# outdoor-sensor.net
KiCad netlist of a schematic drawn in EAGLE
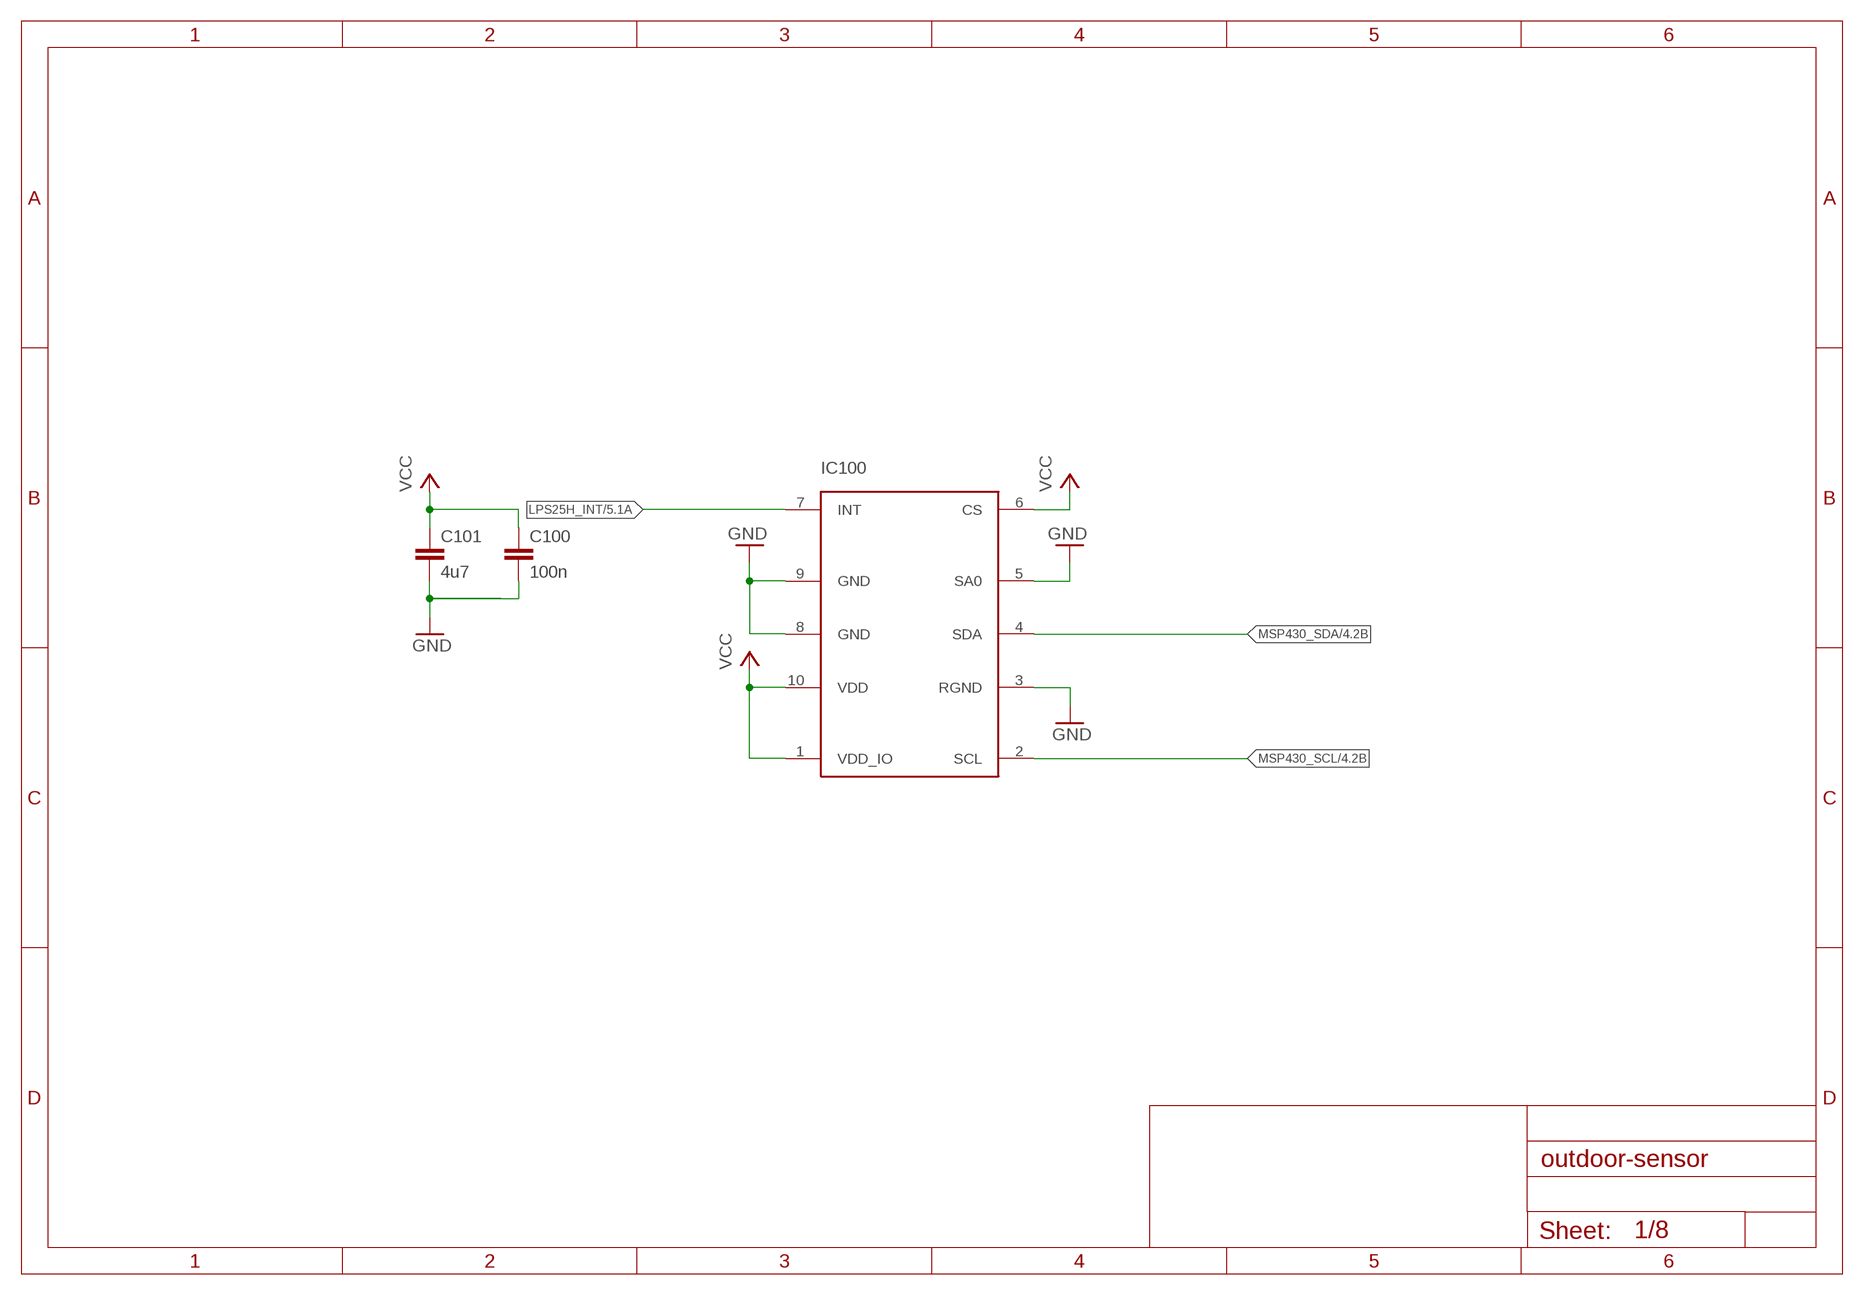
[diagram p0: schematic, sheet 1]
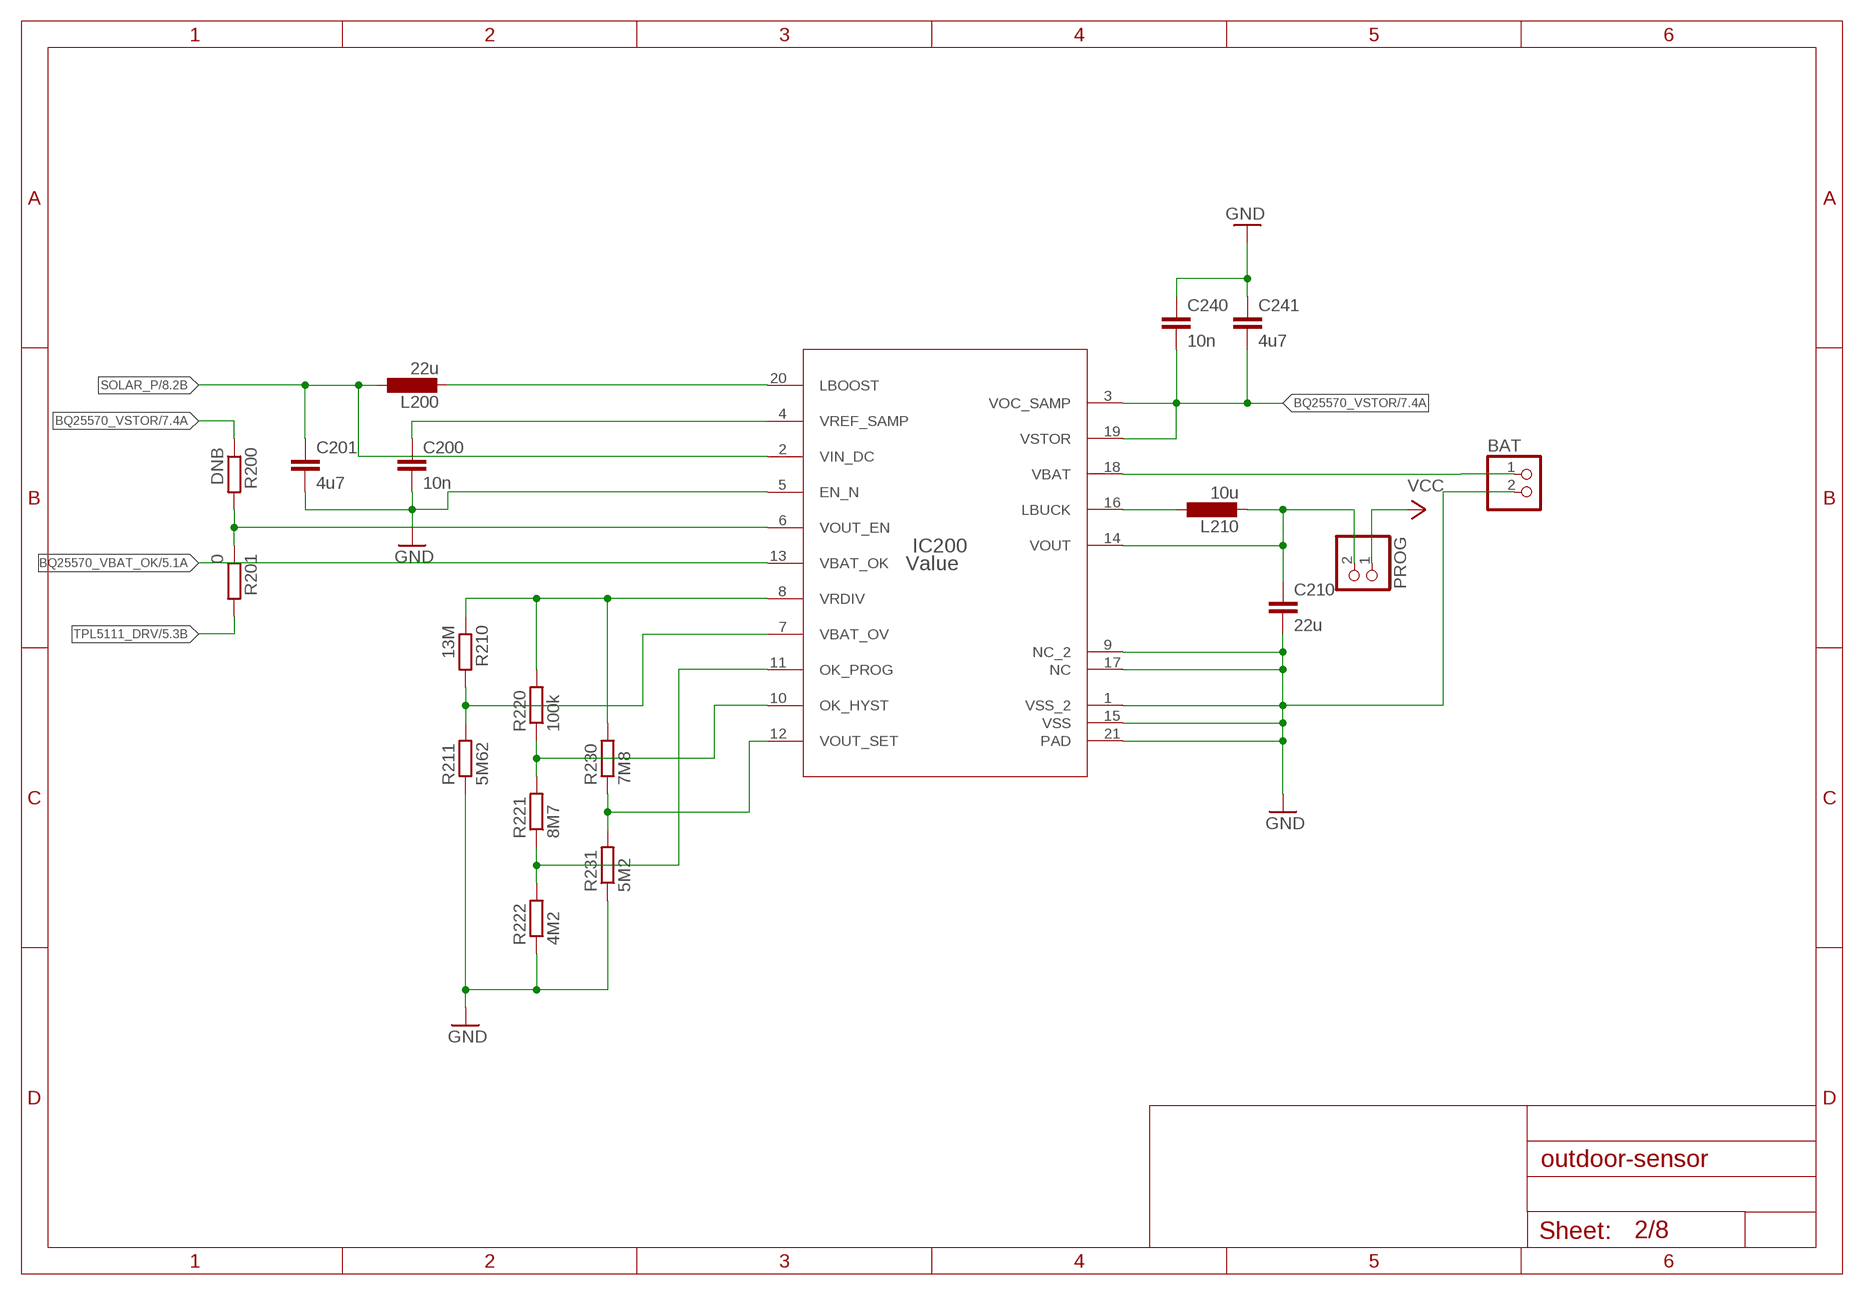
[diagram p1: schematic, sheet 2]
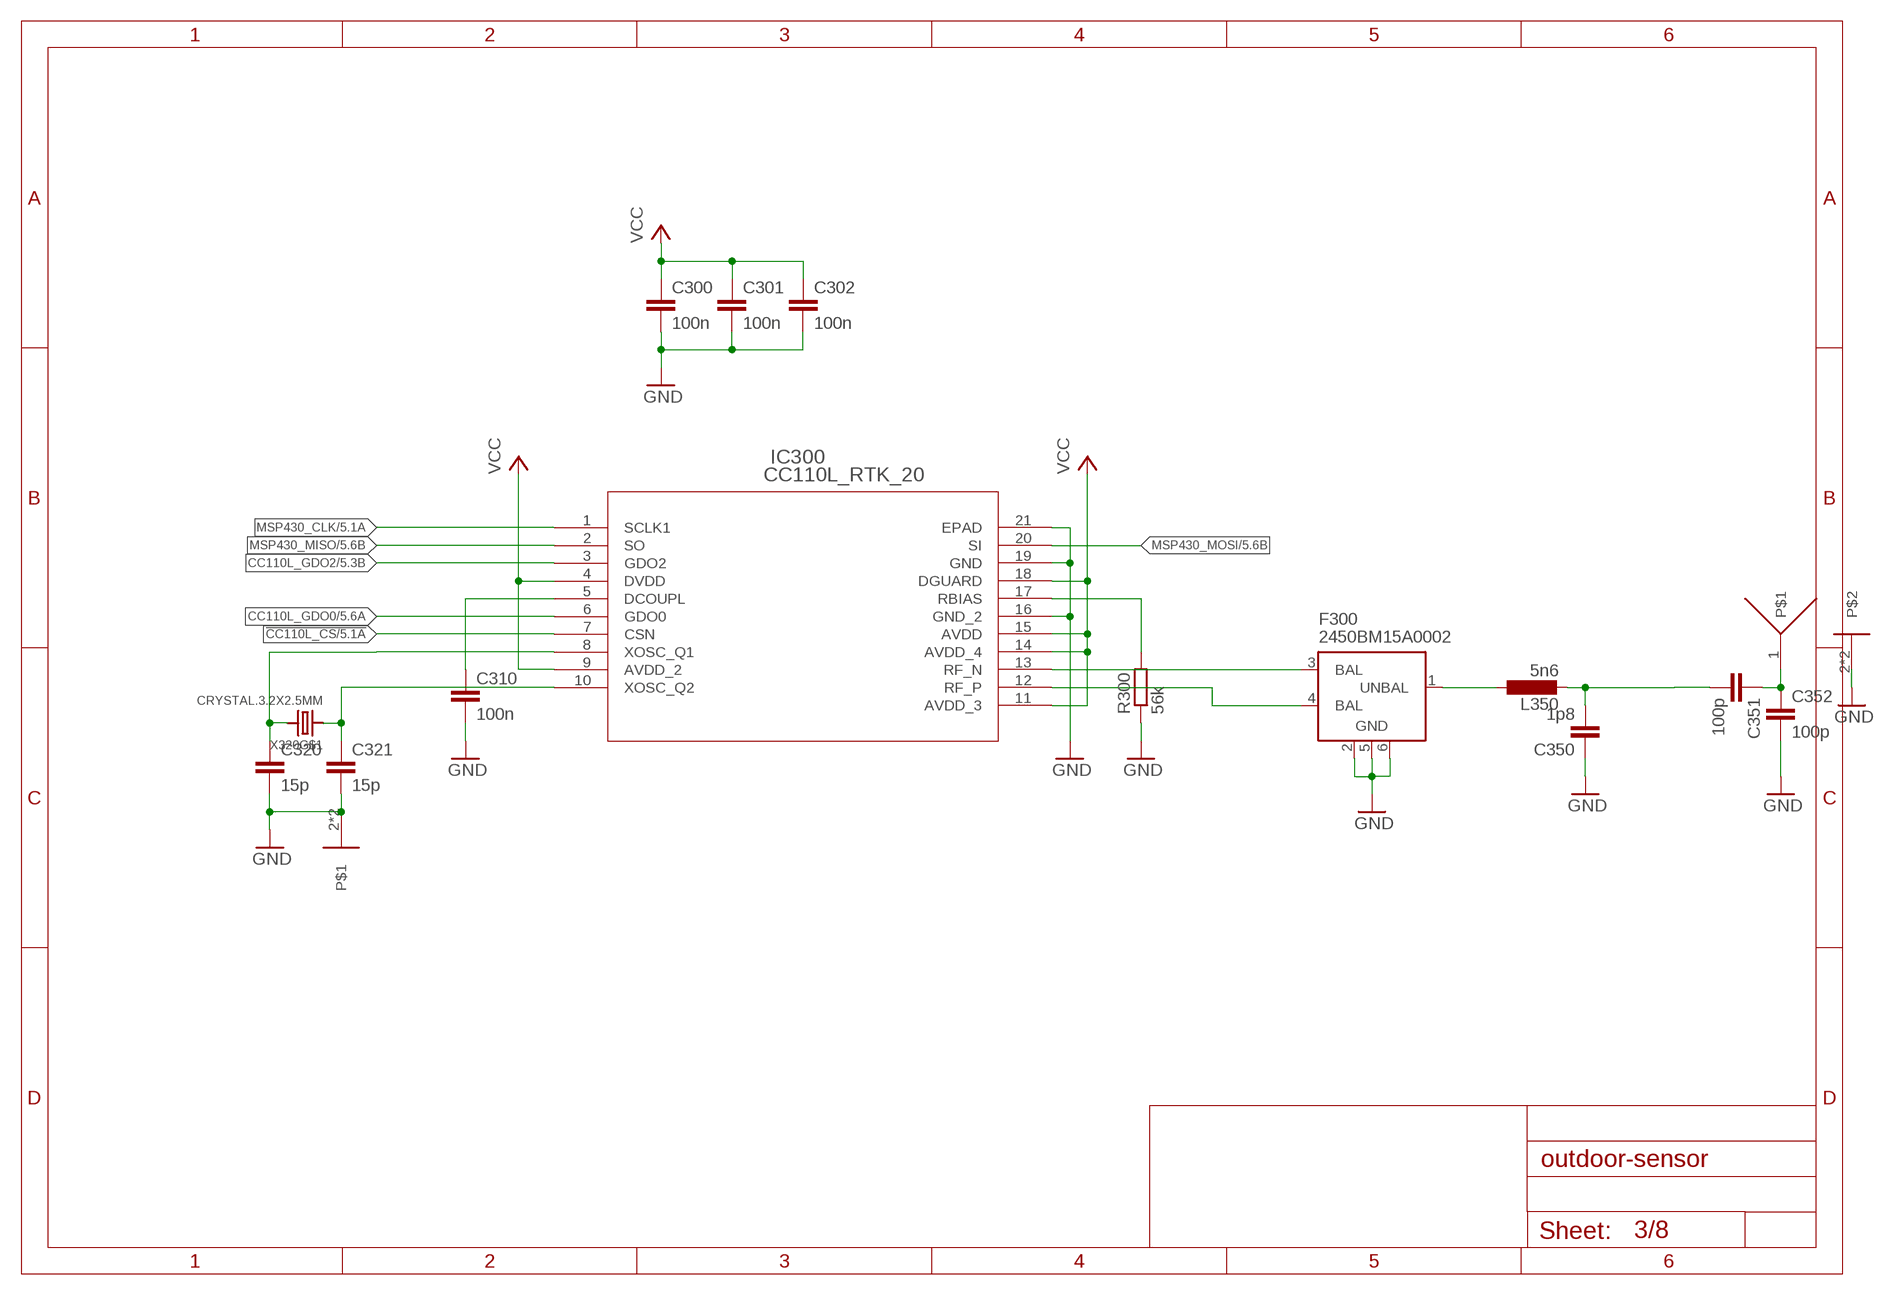
[diagram p2: schematic, sheet 3]
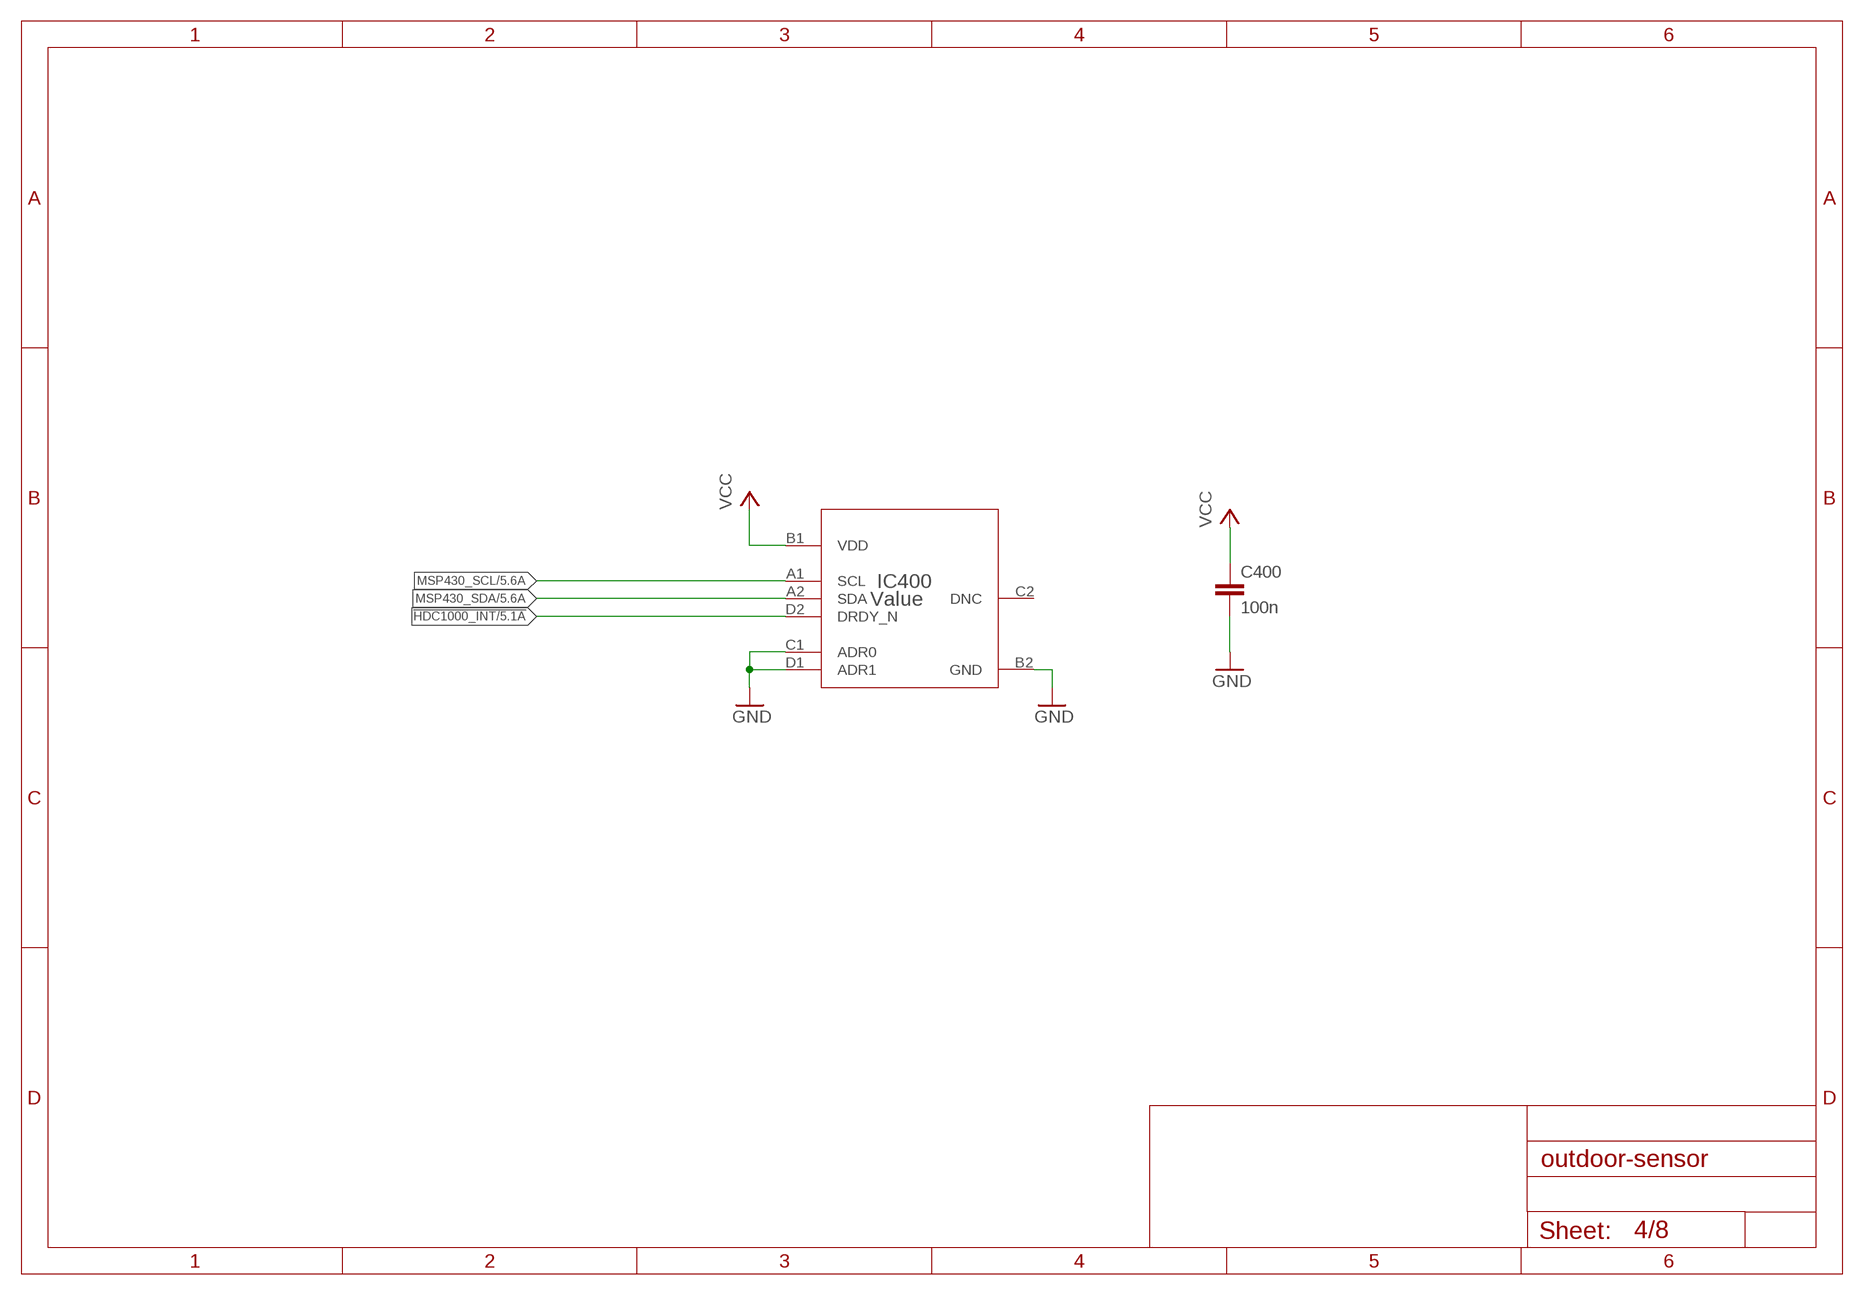
[diagram p3: schematic, sheet 4]
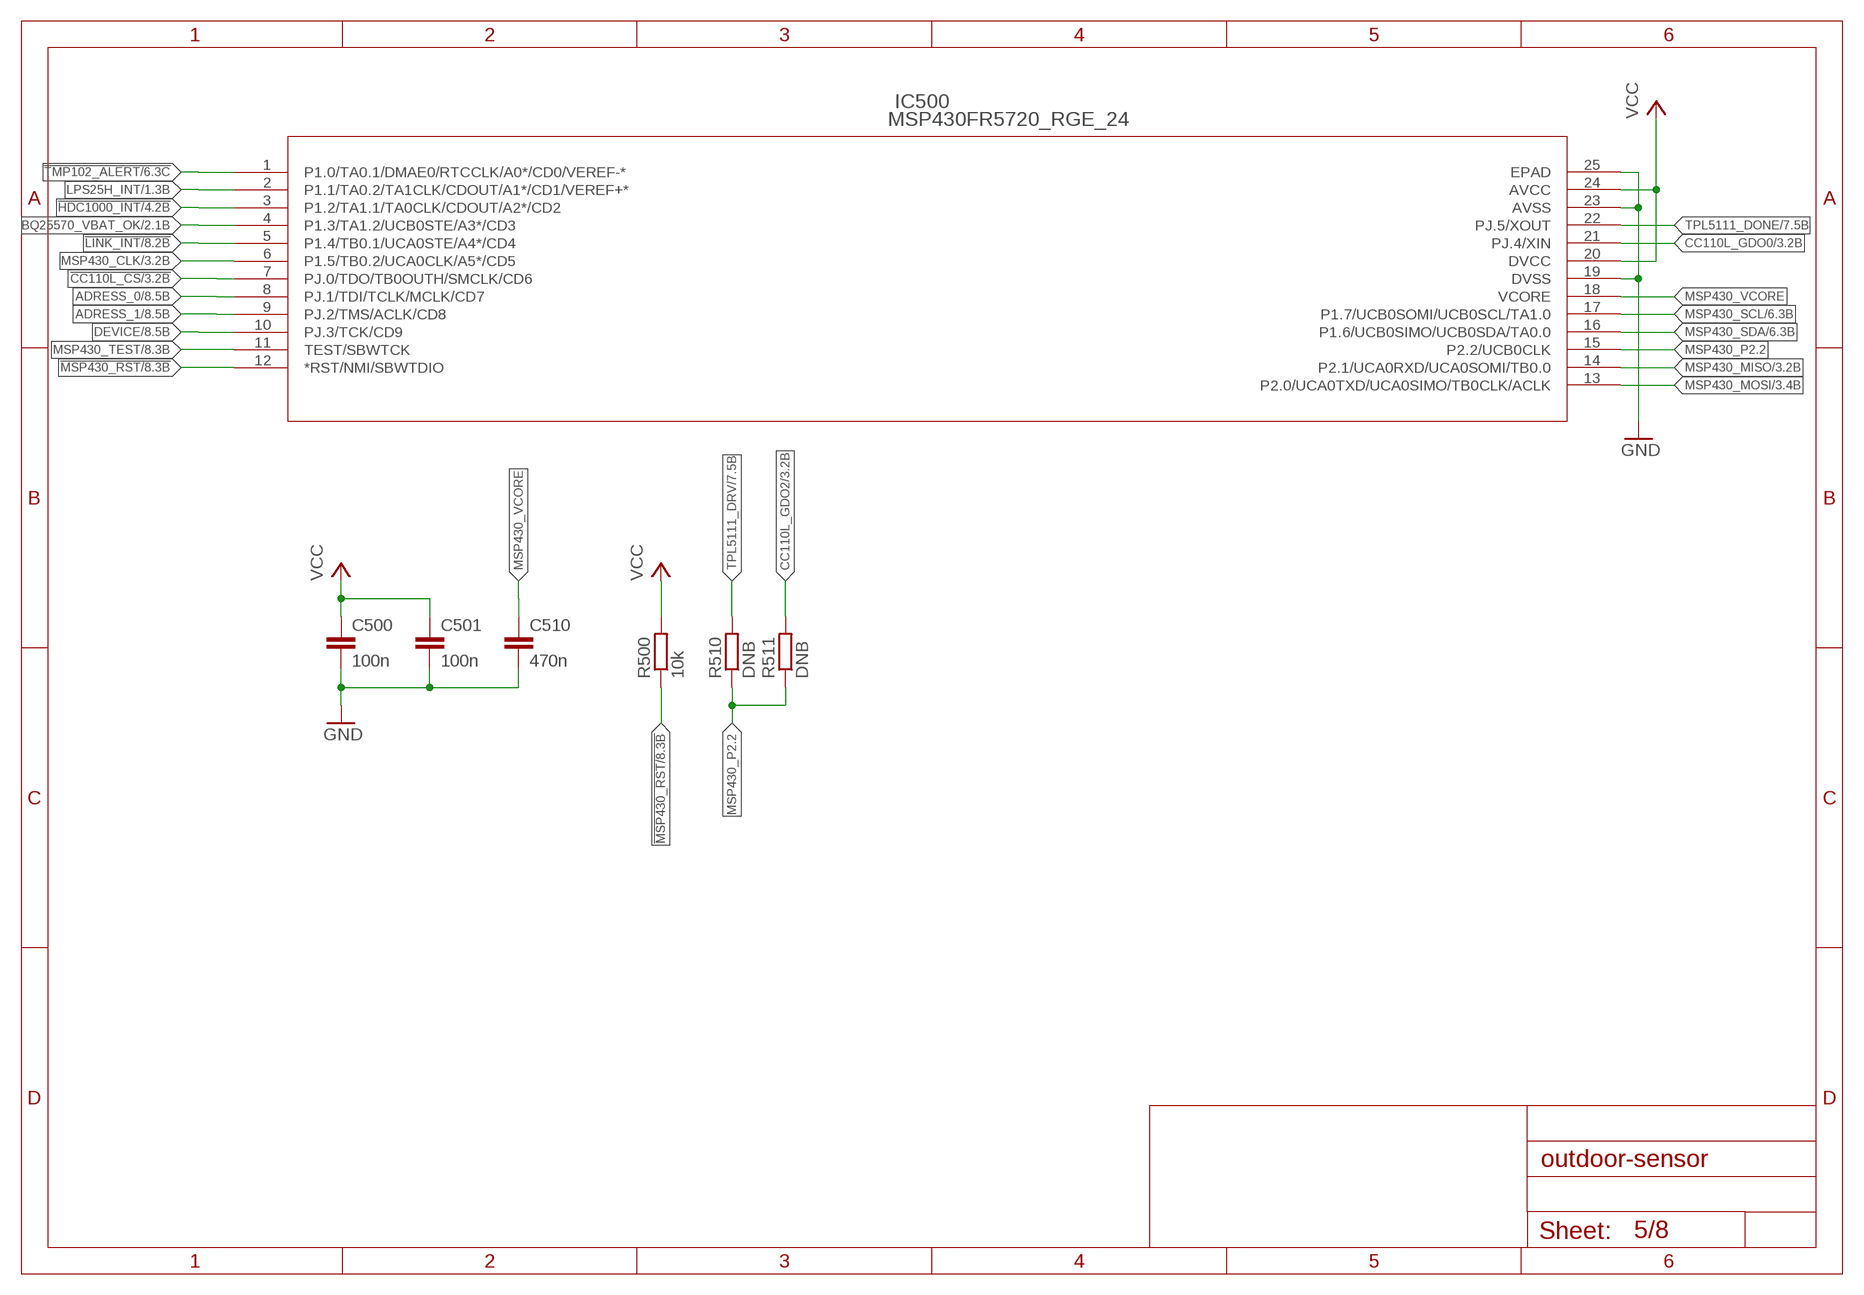
[diagram p4: schematic, sheet 5]
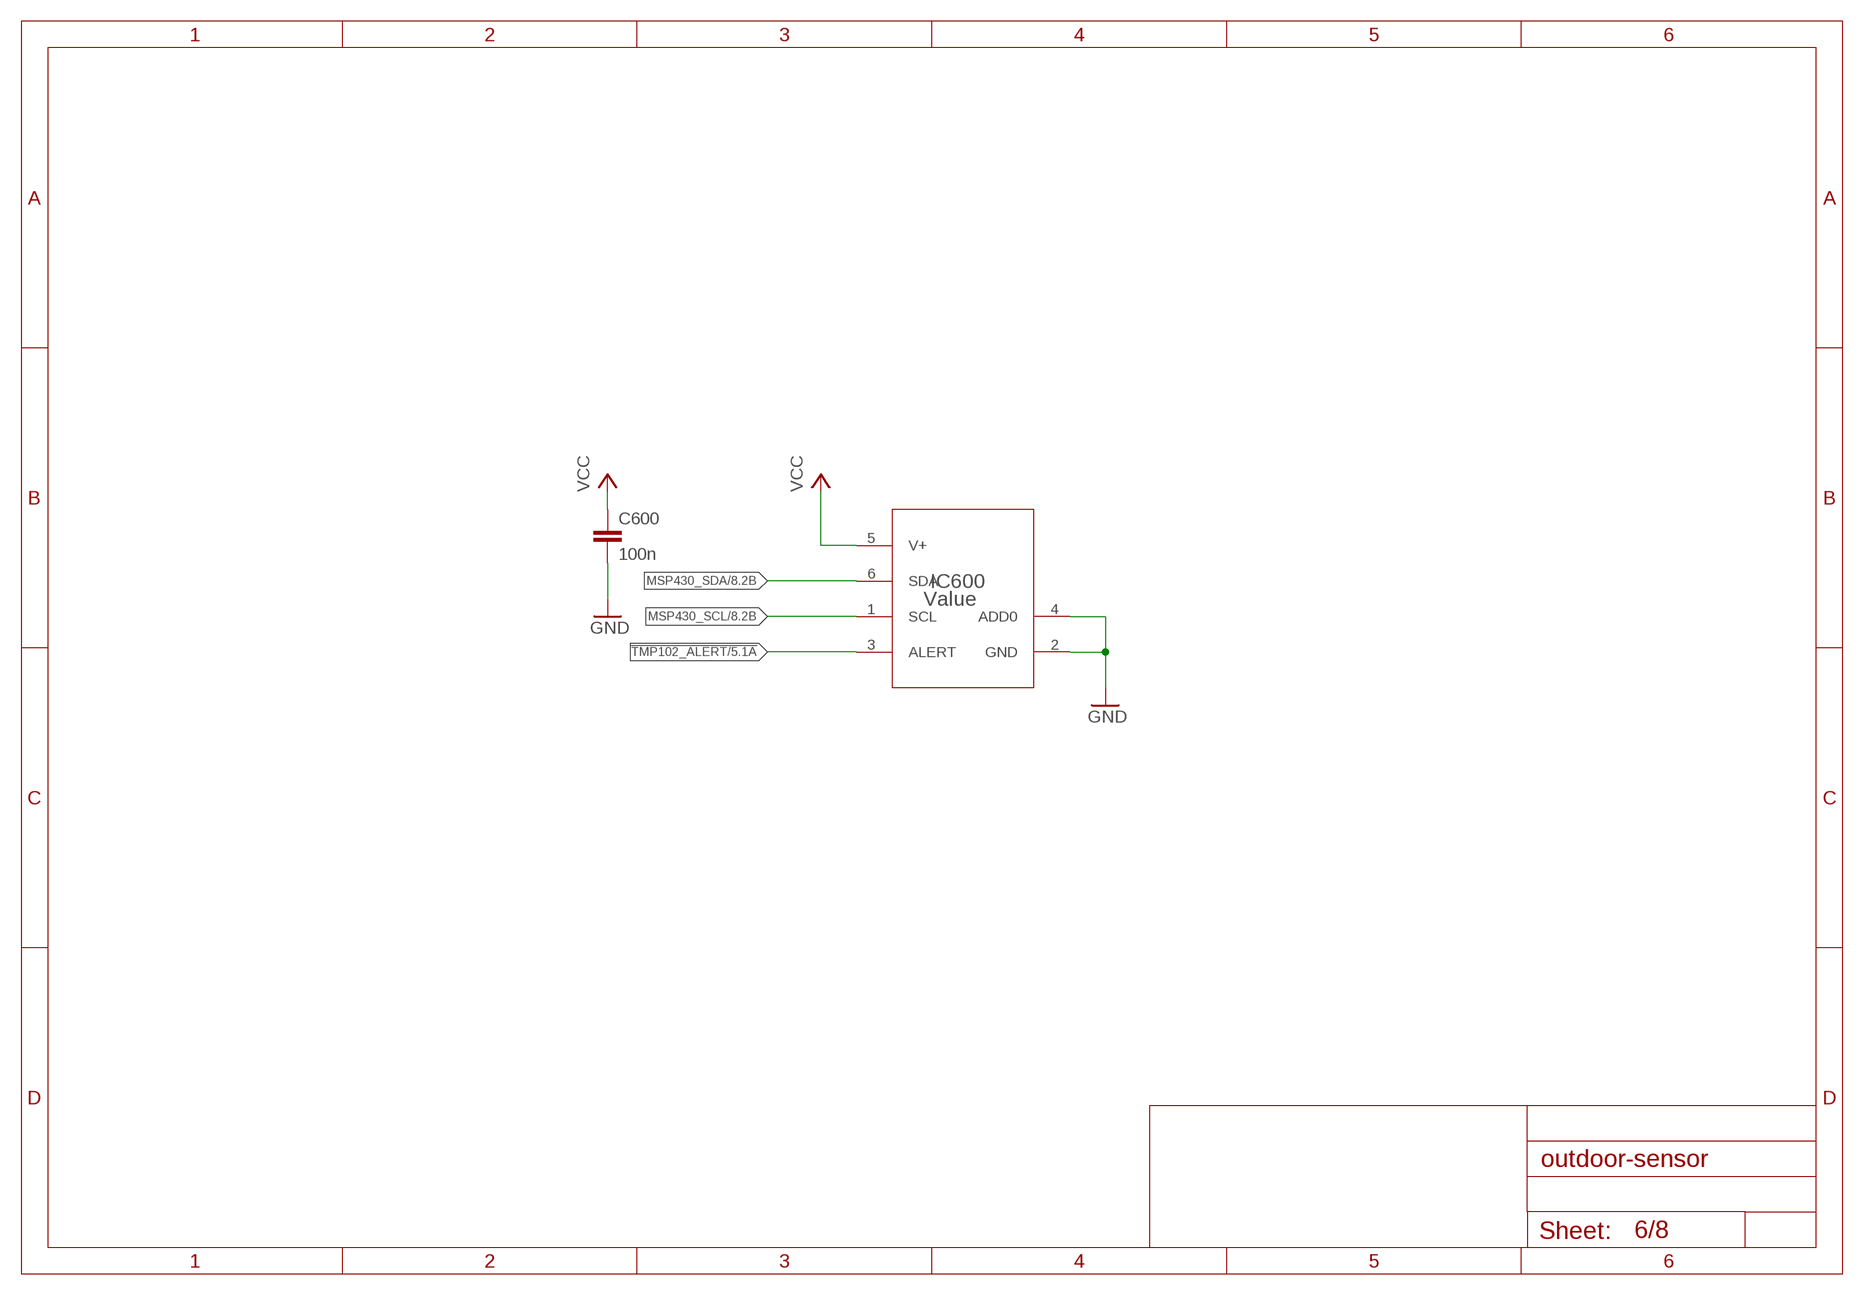
[diagram p5: schematic, sheet 6]
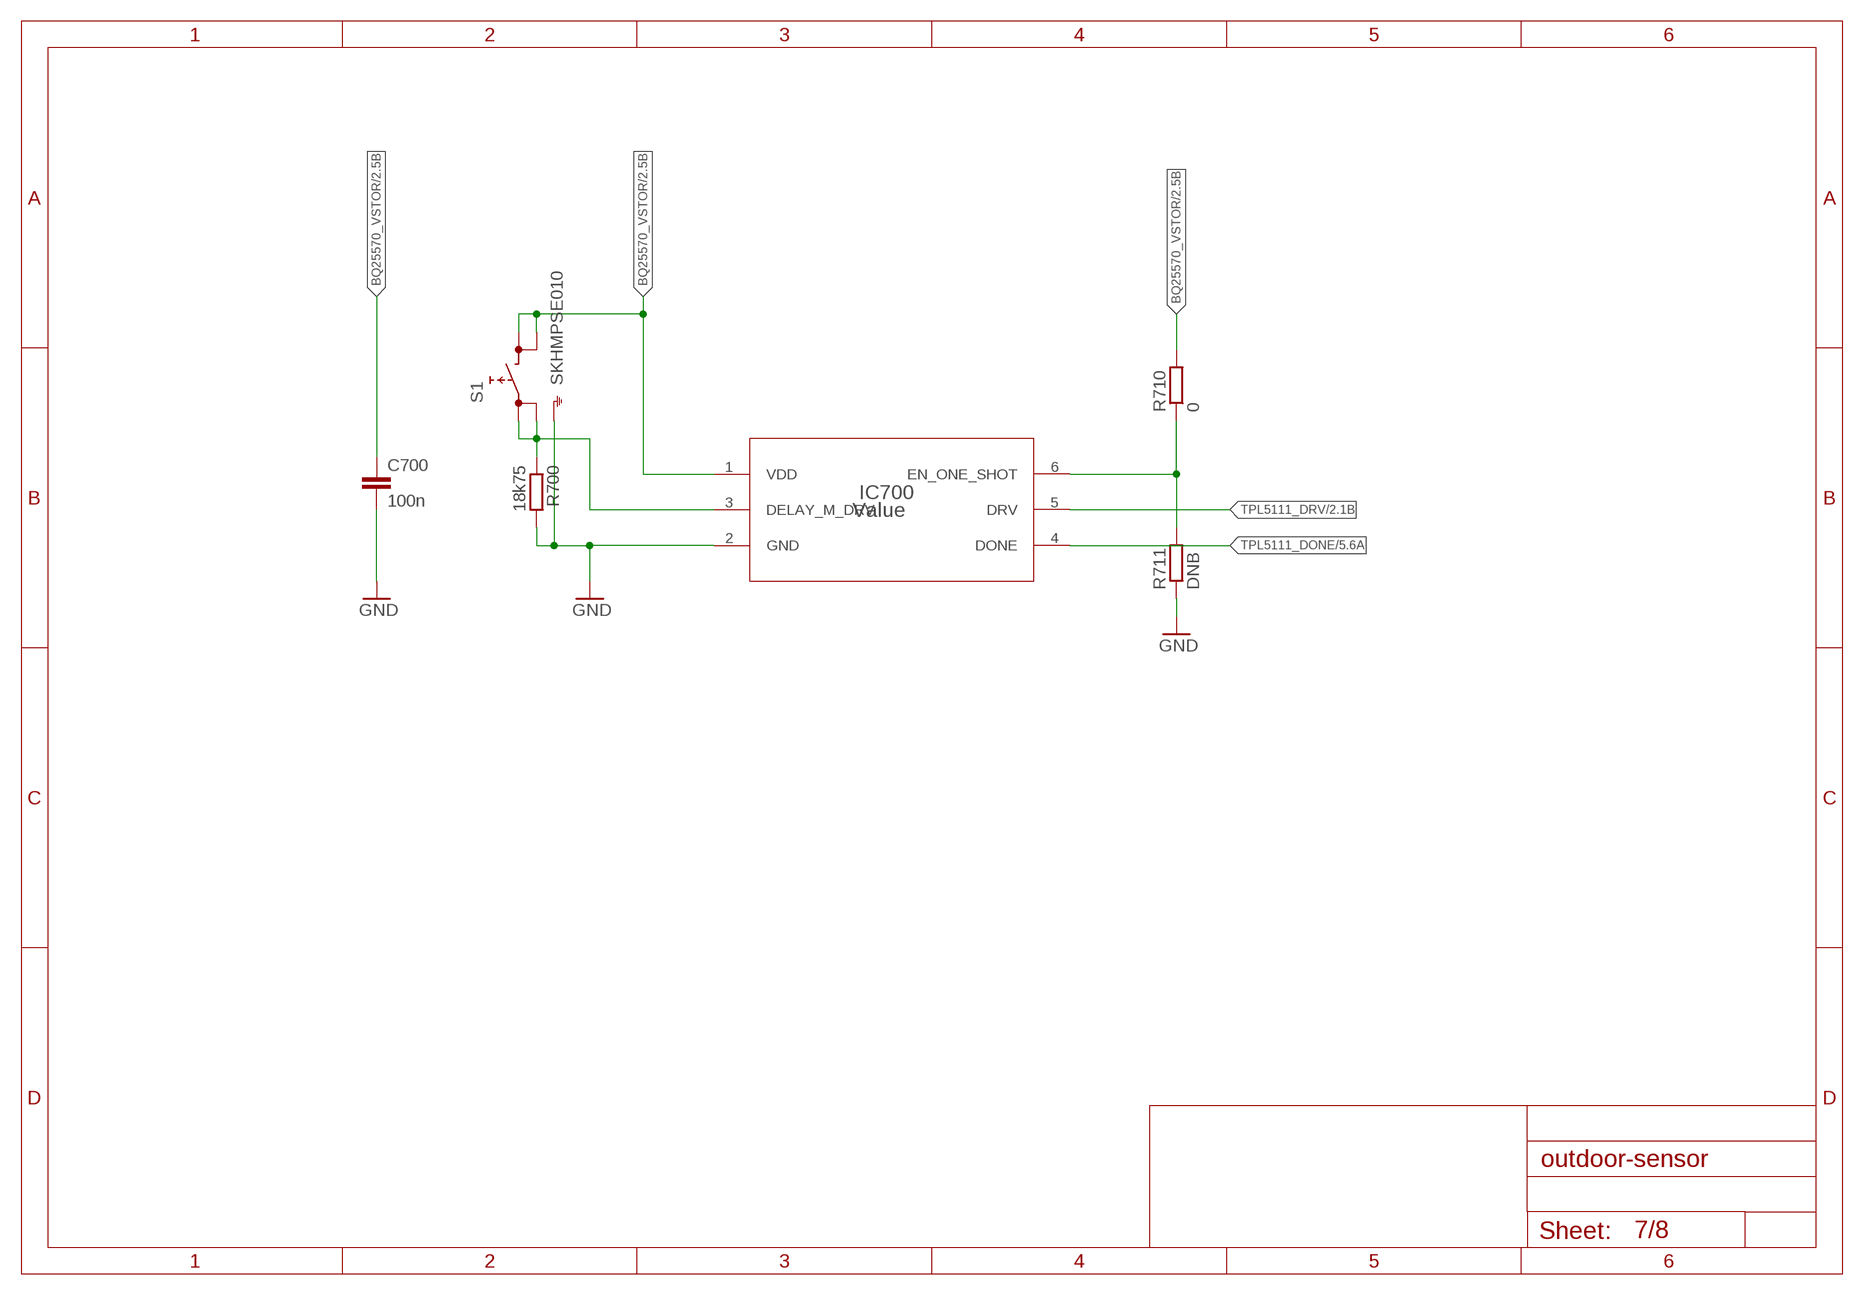
[diagram p6: schematic, sheet 7]
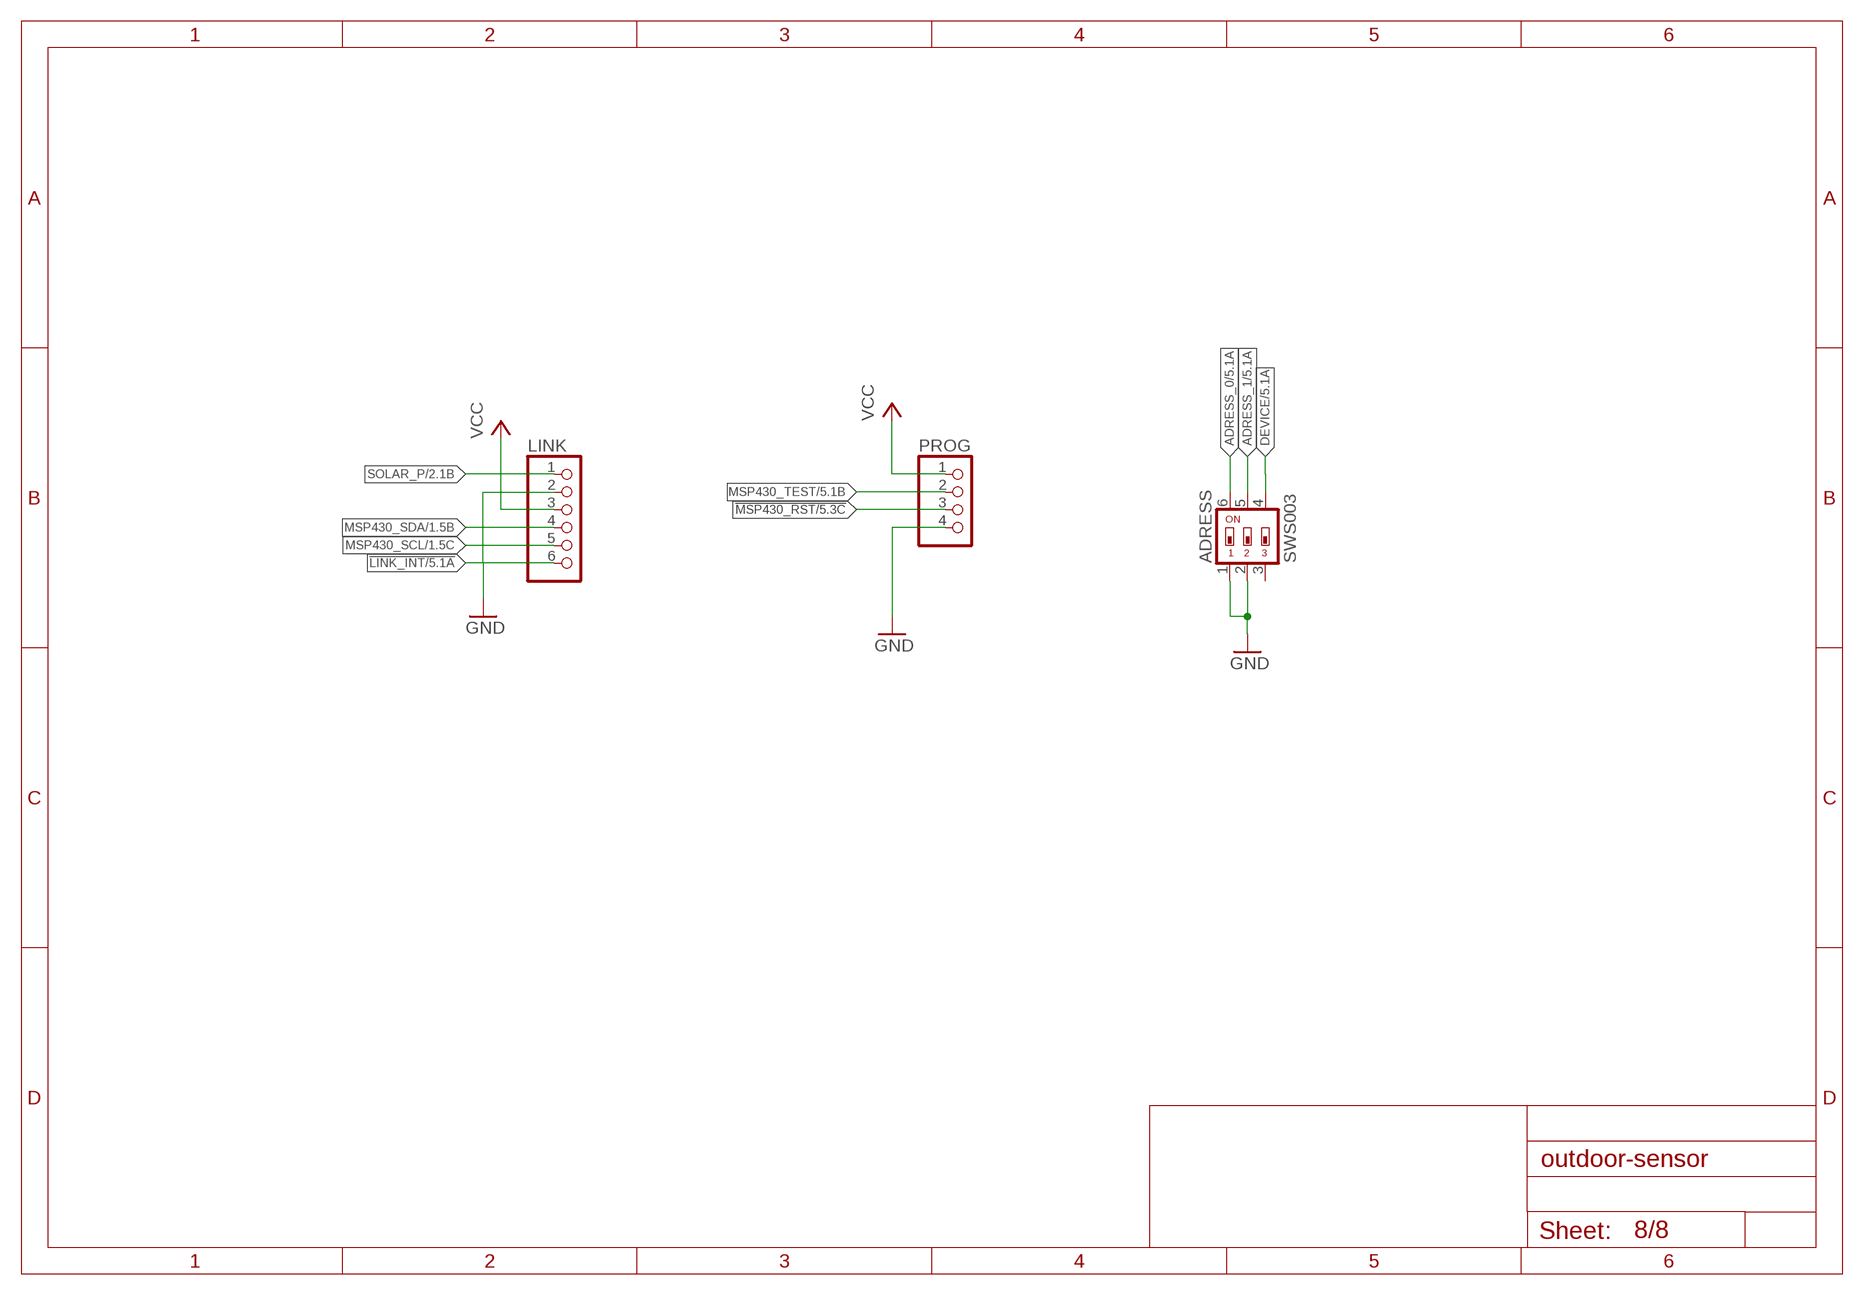
[diagram p7: schematic, sheet 8]

(export (version "E")
  (design (tool "Eeschema 10.0.6"))
  (components
    (comp (ref "C600")
      (value "100n")
      (footprint "eagle-import:C0603")
      (libsource (lib "eagle-import") (part "C-EUC0603"))
    )
    (comp (ref "IC600")
      (value "Value")
      (footprint "eagle-import:DRL0006A")
      (fields (field (name "MANUFACTURER") "Texas Instruments") (field (name "PARTNUMBER") "TMP102AQDRLRQ1"))
      (libsource (lib "eagle-import") (part "TMP102AQDRLRQ1"))
    )
    (comp (ref "ADRESS")
      (value "SWS003")
      (footprint "eagle-import:SMS-003")
      (libsource (lib "eagle-import") (part "SWS003"))
    )
    (comp (ref "LINK")
      (value "PINHD-1X6")
      (footprint "eagle-import:1X06")
      (libsource (lib "eagle-import") (part "PINHD-1X6"))
    )
    (comp (ref "PROG")
      (value "PINHD-1X4")
      (footprint "eagle-import:1X04")
      (libsource (lib "eagle-import") (part "PINHD-1X4"))
    )
    (comp (ref "C700")
      (value "100n")
      (footprint "eagle-import:C0603")
      (libsource (lib "eagle-import") (part "C-EUC0603"))
    )
    (comp (ref "IC700")
      (value "Value")
      (footprint "eagle-import:DDC0006A_N")
      (fields (field (name "MANUFACTURER") "Texas Instruments") (field (name "PARTNUMBER") "TPL5110DDC"))
      (libsource (lib "eagle-import") (part "TPL5110DDCR"))
    )
    (comp (ref "R700")
      (value "18k75")
      (footprint "eagle-import:R0603")
      (libsource (lib "eagle-import") (part "R-EU_R0603"))
    )
    (comp (ref "R710")
      (value "0")
      (footprint "eagle-import:R0603")
      (libsource (lib "eagle-import") (part "R-EU_R0603"))
    )
    (comp (ref "R711")
      (value "DNB")
      (footprint "eagle-import:R0603")
      (libsource (lib "eagle-import") (part "R-EU_R0603"))
    )
    (comp (ref "S1")
      (value "SKHMPSE010")
      (footprint "eagle-import:SKHMPXE010")
      (libsource (lib "eagle-import") (part "SKHMPE010S"))
    )
    (comp (ref "C100")
      (value "100n")
      (footprint "eagle-import:C0603")
      (libsource (lib "eagle-import") (part "C-EUC0603"))
    )
    (comp (ref "C101")
      (value "4u7")
      (footprint "eagle-import:C0603")
      (libsource (lib "eagle-import") (part "C-EUC0603"))
    )
    (comp (ref "IC100")
      (value "LPS25H")
      (footprint "eagle-import:LPS25H")
      (libsource (lib "eagle-import") (part "LPS25H"))
    )
    (comp (ref "C400")
      (value "100n")
      (footprint "eagle-import:C0603")
      (libsource (lib "eagle-import") (part "C-EUC0603"))
    )
    (comp (ref "IC400")
      (value "Value")
      (footprint "eagle-import:YPA0008AGAE")
      (fields
        (field (name "ALTERNATEPARTNUMBER") "HDC1000YPAT")
        (field (name "MANUFACTURER") "Texas Instruments")
        (field (name "PARTNUMBER") "HDC1000YPAR")
      )
      (libsource (lib "eagle-import") (part "HDC1000YPAR"))
    )
    (comp (ref "C300")
      (value "100n")
      (footprint "eagle-import:C0603")
      (libsource (lib "eagle-import") (part "C-EUC0603"))
    )
    (comp (ref "C301")
      (value "100n")
      (footprint "eagle-import:C0603")
      (libsource (lib "eagle-import") (part "C-EUC0603"))
    )
    (comp (ref "C302")
      (value "100n")
      (footprint "eagle-import:C0603")
      (libsource (lib "eagle-import") (part "C-EUC0603"))
    )
    (comp (ref "C310")
      (value "100n")
      (footprint "eagle-import:C0603")
      (libsource (lib "eagle-import") (part "C-EUC0603"))
    )
    (comp (ref "C320")
      (value "15p")
      (footprint "eagle-import:C0603")
      (libsource (lib "eagle-import") (part "C-EUC0603"))
    )
    (comp (ref "C321")
      (value "15p")
      (footprint "eagle-import:C0603")
      (libsource (lib "eagle-import") (part "C-EUC0603"))
    )
    (comp (ref "C350")
      (value "1p8")
      (footprint "eagle-import:C0603K")
      (libsource (lib "eagle-import") (part "C-EUC0603K"))
    )
    (comp (ref "C351")
      (value "100p")
      (footprint "eagle-import:C0603")
      (libsource (lib "eagle-import") (part "C-EUC0603"))
    )
    (comp (ref "C352")
      (value "100p")
      (footprint "eagle-import:C0603K")
      (libsource (lib "eagle-import") (part "C-EUC0603K"))
    )
    (comp (ref "F300")
      (value "2450BM15A0002")
      (footprint "eagle-import:2450BM15A0002")
      (libsource (lib "eagle-import") (part "2450BM15A0002"))
    )
    (comp (ref "IC300")
      (value "CC110L_RTK_20")
      (footprint "eagle-import:RTK20_2P4X2P4")
      (fields (field (name "GENERIC_PART_NUMBER") "CC110L") (field (name "MANUFACTURER") "Texas Instruments"))
      (libsource (lib "eagle-import") (part "CC110L_RTK_20"))
    )
    (comp (ref "L350")
      (value "5n6")
      (footprint "eagle-import:L2012C")
      (libsource (lib "eagle-import") (part "L-EUL2012C"))
    )
    (comp (ref "R300")
      (value "56k")
      (footprint "eagle-import:R0603")
      (libsource (lib "eagle-import") (part "R-EU_R0603"))
    )
    (comp (ref "U$1")
      (value "ANTENNA868W3013-INV")
      (footprint "eagle-import:W3013-INV")
      (libsource (lib "eagle-import") (part "ANTENNA868W3013-INV"))
    )
    (comp (ref "X320")
      (value "CRYSTAL.3.2X2.5MM")
      (footprint "eagle-import:3.2X2.5MM")
      (libsource (lib "eagle-import") (part "CRYSTAL.3.2X2.5MM"))
    )
    (comp (ref "C500")
      (value "100n")
      (footprint "eagle-import:C0603")
      (libsource (lib "eagle-import") (part "C-EUC0603"))
    )
    (comp (ref "C501")
      (value "100n")
      (footprint "eagle-import:C0603")
      (libsource (lib "eagle-import") (part "C-EUC0603"))
    )
    (comp (ref "C510")
      (value "470n")
      (footprint "eagle-import:C0603")
      (libsource (lib "eagle-import") (part "C-EUC0603"))
    )
    (comp (ref "IC500")
      (value "MSP430FR5720_RGE_24")
      (footprint "eagle-import:RGE24_2P1X2P1")
      (fields
        (field (name "GENERIC_PART_NUMBER") "MSP430FR5720")
        (field (name "MANUFACTURER") "Texas Instruments")
        (field (name "MANUFACTURER_PART_NUMBER") "msp430fr5720_rge_24")
      )
      (libsource (lib "eagle-import") (part "MSP430FR5720_RGE_24"))
    )
    (comp (ref "R500")
      (value "10k")
      (footprint "eagle-import:R0603")
      (libsource (lib "eagle-import") (part "R-EU_R0603"))
    )
    (comp (ref "R510")
      (value "DNB")
      (footprint "eagle-import:R0603")
      (libsource (lib "eagle-import") (part "R-EU_R0603"))
    )
    (comp (ref "R511")
      (value "DNB")
      (footprint "eagle-import:R0603")
      (libsource (lib "eagle-import") (part "R-EU_R0603"))
    )
    (comp (ref "!PROG")
      (value "PINHD-1X2")
      (footprint "eagle-import:1X02")
      (libsource (lib "eagle-import") (part "PINHD-1X2"))
    )
    (comp (ref "BAT")
      (value "PINHD-1X2")
      (footprint "eagle-import:1X02")
      (libsource (lib "eagle-import") (part "PINHD-1X2"))
    )
    (comp (ref "C200")
      (value "10n")
      (footprint "eagle-import:C0603")
      (libsource (lib "eagle-import") (part "C-EUC0603"))
    )
    (comp (ref "C201")
      (value "4u7")
      (footprint "eagle-import:C0603")
      (libsource (lib "eagle-import") (part "C-EUC0603"))
    )
    (comp (ref "C210")
      (value "22u")
      (footprint "eagle-import:C0603")
      (libsource (lib "eagle-import") (part "C-EUC0603"))
    )
    (comp (ref "C240")
      (value "10n")
      (footprint "eagle-import:C0603")
      (libsource (lib "eagle-import") (part "C-EUC0603"))
    )
    (comp (ref "C241")
      (value "4u7")
      (footprint "eagle-import:C0603")
      (libsource (lib "eagle-import") (part "C-EUC0603"))
    )
    (comp (ref "IC200")
      (value "Value")
      (footprint "eagle-import:RGR0020A")
      (fields
        (field (name "ALTERNATEPARTNUMBER") "BQ25570RGRT")
        (field (name "MANUFACTURER") "Texas Instruments")
        (field (name "PARTNUMBER") "BQ25570RGRR")
      )
      (libsource (lib "eagle-import") (part "BQ25570RGRR"))
    )
    (comp (ref "L200")
      (value "22u")
      (footprint "eagle-import:L3225P")
      (libsource (lib "eagle-import") (part "L-EUL3225P"))
    )
    (comp (ref "L210")
      (value "10u")
      (footprint "eagle-import:L3225P")
      (libsource (lib "eagle-import") (part "L-EUL3225P"))
    )
    (comp (ref "R200")
      (value "DNB")
      (footprint "eagle-import:R0603")
      (libsource (lib "eagle-import") (part "R-EU_R0603"))
    )
    (comp (ref "R201")
      (value "0")
      (footprint "eagle-import:R0603")
      (libsource (lib "eagle-import") (part "R-EU_R0603"))
    )
    (comp (ref "R210")
      (value "13M")
      (footprint "eagle-import:R0603")
      (libsource (lib "eagle-import") (part "R-EU_R0603"))
    )
    (comp (ref "R211")
      (value "5M62")
      (footprint "eagle-import:R0603")
      (libsource (lib "eagle-import") (part "R-EU_R0603"))
    )
    (comp (ref "R220")
      (value "100k")
      (footprint "eagle-import:R0603")
      (libsource (lib "eagle-import") (part "R-EU_R0603"))
    )
    (comp (ref "R221")
      (value "8M7")
      (footprint "eagle-import:R0603")
      (libsource (lib "eagle-import") (part "R-EU_R0603"))
    )
    (comp (ref "R222")
      (value "4M2")
      (footprint "eagle-import:R0603")
      (libsource (lib "eagle-import") (part "R-EU_R0603"))
    )
    (comp (ref "R230")
      (value "7M8")
      (footprint "eagle-import:R0603")
      (libsource (lib "eagle-import") (part "R-EU_R0603"))
    )
    (comp (ref "R231")
      (value "5M2")
      (footprint "eagle-import:R0603")
      (libsource (lib "eagle-import") (part "R-EU_R0603"))
    )
  )
  (nets
    (net (code "1") (name "ADRESS_0") (class "Default")
      (node (ref "ADRESS") (pin "6") (pinfunction "6_6") (pintype "passive"))
      (node (ref "IC500") (pin "8") (pinfunction "PJ.1/TDI/TCLK/MCLK/CD7_8") (pintype "bidirectional"))
    )
    (net (code "2") (name "ADRESS_1") (class "Default")
      (node (ref "ADRESS") (pin "5") (pinfunction "5_5") (pintype "passive"))
      (node (ref "IC500") (pin "9") (pinfunction "PJ.2/TMS/ACLK/CD8_9") (pintype "bidirectional"))
    )
    (net (code "3") (name "BQ25570_VBAT_OK") (class "Default")
      (node (ref "IC200") (pin "13") (pinfunction "VBAT_OK_13") (pintype "output"))
      (node (ref "IC500") (pin "4") (pinfunction "P1.3/TA1.2/UCB0STE/A3*/CD3_4") (pintype "bidirectional"))
    )
    (net (code "4") (name "BQ25570_VSTOR") (class "Default")
      (node (ref "C240") (pin "2") (pinfunction "2_2") (pintype "passive"))
      (node (ref "C241") (pin "2") (pinfunction "2_2") (pintype "passive"))
      (node (ref "C700") (pin "1") (pinfunction "1_1") (pintype "passive"))
      (node (ref "IC200") (pin "19") (pinfunction "VSTOR_19") (pintype "power_in"))
      (node (ref "IC200") (pin "3") (pinfunction "VOC_SAMP_3") (pintype "input"))
      (node (ref "IC700") (pin "1") (pinfunction "VDD_1") (pintype "power_in"))
      (node (ref "R200") (pin "1") (pinfunction "1_1") (pintype "passive"))
      (node (ref "R710") (pin "2") (pinfunction "2_2") (pintype "passive"))
      (node (ref "S1") (pin "3") (pinfunction "2.1_3") (pintype "passive"))
      (node (ref "S1") (pin "4") (pinfunction "2.2_4") (pintype "passive"))
    )
    (net (code "5") (name "CC110L_GDO0") (class "Default")
      (node (ref "IC300") (pin "6") (pinfunction "GDO0_6") (pintype "output"))
      (node (ref "IC500") (pin "21") (pinfunction "PJ.4/XIN_21") (pintype "bidirectional"))
    )
    (net (code "6") (name "CC110L_GDO2") (class "Default")
      (node (ref "IC300") (pin "3") (pinfunction "GDO2_3") (pintype "output"))
      (node (ref "R511") (pin "2") (pinfunction "2_2") (pintype "passive"))
    )
    (net (code "7") (name "DEVICE") (class "Default")
      (node (ref "ADRESS") (pin "4") (pinfunction "4_4") (pintype "passive"))
      (node (ref "IC500") (pin "10") (pinfunction "PJ.3/TCK/CD9_10") (pintype "bidirectional"))
    )
    (net (code "8") (name "GND") (class "Default")
      (node (ref "ADRESS") (pin "1") (pinfunction "1_1") (pintype "passive"))
      (node (ref "ADRESS") (pin "2") (pinfunction "2_2") (pintype "passive"))
      (node (ref "BAT") (pin "2") (pinfunction "2_2") (pintype "passive"))
      (node (ref "C100") (pin "2") (pinfunction "2_2") (pintype "passive"))
      (node (ref "C101") (pin "2") (pinfunction "2_2") (pintype "passive"))
      (node (ref "C200") (pin "2") (pinfunction "2_2") (pintype "passive"))
      (node (ref "C201") (pin "2") (pinfunction "2_2") (pintype "passive"))
      (node (ref "C210") (pin "2") (pinfunction "2_2") (pintype "passive"))
      (node (ref "C240") (pin "1") (pinfunction "1_1") (pintype "passive"))
      (node (ref "C241") (pin "1") (pinfunction "1_1") (pintype "passive"))
      (node (ref "C300") (pin "2") (pinfunction "2_2") (pintype "passive"))
      (node (ref "C301") (pin "2") (pinfunction "2_2") (pintype "passive"))
      (node (ref "C302") (pin "2") (pinfunction "2_2") (pintype "passive"))
      (node (ref "C310") (pin "2") (pinfunction "2_2") (pintype "passive"))
      (node (ref "C320") (pin "2") (pinfunction "2_2") (pintype "passive"))
      (node (ref "C321") (pin "2") (pinfunction "2_2") (pintype "passive"))
      (node (ref "C350") (pin "1") (pinfunction "1_1") (pintype "passive"))
      (node (ref "C352") (pin "2") (pinfunction "2_2") (pintype "passive"))
      (node (ref "C400") (pin "2") (pinfunction "2_2") (pintype "passive"))
      (node (ref "C500") (pin "2") (pinfunction "2_2") (pintype "passive"))
      (node (ref "C501") (pin "2") (pinfunction "2_2") (pintype "passive"))
      (node (ref "C510") (pin "2") (pinfunction "2_2") (pintype "passive"))
      (node (ref "C600") (pin "2") (pinfunction "2_2") (pintype "passive"))
      (node (ref "C700") (pin "2") (pinfunction "2_2") (pintype "passive"))
      (node (ref "F300") (pin "2") (pinfunction "GND_2") (pintype "passive"))
      (node (ref "F300") (pin "5") (pinfunction "GND_5") (pintype "passive"))
      (node (ref "F300") (pin "6") (pinfunction "GND_6") (pintype "passive"))
      (node (ref "IC100") (pin "3") (pinfunction "RGND_3") (pintype "bidirectional"))
      (node (ref "IC100") (pin "5") (pinfunction "SA0_5") (pintype "bidirectional"))
      (node (ref "IC100") (pin "8") (pinfunction "GND_8") (pintype "power_in"))
      (node (ref "IC100") (pin "9") (pinfunction "GND_9") (pintype "power_in"))
      (node (ref "IC200") (pin "1") (pinfunction "VSS_2_1") (pintype "power_in"))
      (node (ref "IC200") (pin "15") (pinfunction "VSS_15") (pintype "power_in"))
      (node (ref "IC200") (pin "17") (pinfunction "NC_17") (pintype "passive"))
      (node (ref "IC200") (pin "21") (pinfunction "PAD_21") (pintype "power_in"))
      (node (ref "IC200") (pin "5") (pinfunction "EN_N_5") (pintype "input"))
      (node (ref "IC200") (pin "9") (pinfunction "NC_2_9") (pintype "power_in"))
      (node (ref "IC300") (pin "16") (pinfunction "GND_2_16") (pintype "power_in"))
      (node (ref "IC300") (pin "19") (pinfunction "GND_19") (pintype "power_in"))
      (node (ref "IC300") (pin "21") (pinfunction "EPAD_21") (pintype "power_in"))
      (node (ref "IC400") (pin "B2") (pinfunction "GND_B2") (pintype "power_in"))
      (node (ref "IC400") (pin "C1") (pinfunction "ADR0_C1") (pintype "input"))
      (node (ref "IC400") (pin "D1") (pinfunction "ADR1_D1") (pintype "input"))
      (node (ref "IC500") (pin "19") (pinfunction "DVSS_19") (pintype "power_in"))
      (node (ref "IC500") (pin "23") (pinfunction "AVSS_23") (pintype "power_in"))
      (node (ref "IC500") (pin "25") (pinfunction "EPAD_25") (pintype "passive"))
      (node (ref "IC600") (pin "2") (pinfunction "GND_2") (pintype "power_in"))
      (node (ref "IC600") (pin "4") (pinfunction "ADD0_4") (pintype "input"))
      (node (ref "IC700") (pin "2") (pinfunction "GND_2") (pintype "power_in"))
      (node (ref "LINK") (pin "2") (pinfunction "2_2") (pintype "passive"))
      (node (ref "PROG") (pin "4") (pinfunction "4_4") (pintype "passive"))
      (node (ref "R211") (pin "1") (pinfunction "1_1") (pintype "passive"))
      (node (ref "R222") (pin "1") (pinfunction "1_1") (pintype "passive"))
      (node (ref "R231") (pin "1") (pinfunction "1_1") (pintype "passive"))
      (node (ref "R300") (pin "1") (pinfunction "1_1") (pintype "passive"))
      (node (ref "R700") (pin "2") (pinfunction "2_2") (pintype "passive"))
      (node (ref "R711") (pin "1") (pinfunction "1_1") (pintype "passive"))
      (node (ref "S1") (pin "5") (pinfunction "SH_5") (pintype "passive"))
      (node (ref "U$1") (pin "2") (pinfunction "P$2_2") (pintype "bidirectional"))
      (node (ref "U$1") (pin "3") (pinfunction "P$2_3") (pintype "bidirectional"))
      (node (ref "X320") (pin "2") (pinfunction "P$1_2") (pintype "bidirectional"))
      (node (ref "X320") (pin "4") (pinfunction "P$1_4") (pintype "bidirectional"))
    )
    (net (code "9") (name "LPS25H_INT") (class "Default")
      (node (ref "IC100") (pin "7") (pinfunction "INT_7") (pintype "bidirectional"))
      (node (ref "IC500") (pin "2") (pinfunction "P1.1/TA0.2/TA1CLK/CDOUT/A1*/CD1/VEREF+*_2") (pintype "bidirectional"))
    )
    (net (code "10") (name "MSP430_CLK") (class "Default")
      (node (ref "IC300") (pin "1") (pinfunction "SCLK1_1") (pintype "passive"))
      (node (ref "IC500") (pin "6") (pinfunction "P1.5/TB0.2/UCA0CLK/A5*/CD5_6") (pintype "bidirectional"))
    )
    (net (code "11") (name "MSP430_MISO") (class "Default")
      (node (ref "IC300") (pin "2") (pinfunction "SO_2") (pintype "output"))
      (node (ref "IC500") (pin "14") (pinfunction "P2.1/UCA0RXD/UCA0SOMI/TB0.0_14") (pintype "bidirectional"))
    )
    (net (code "12") (name "MSP430_MOSI") (class "Default")
      (node (ref "IC300") (pin "20") (pinfunction "SI_20") (pintype "input"))
      (node (ref "IC500") (pin "13") (pinfunction "P2.0/UCA0TXD/UCA0SIMO/TB0CLK/ACLK_13") (pintype "bidirectional"))
    )
    (net (code "13") (name "MSP430_P2.2") (class "Default")
      (node (ref "IC500") (pin "15") (pinfunction "P2.2/UCB0CLK_15") (pintype "bidirectional"))
      (node (ref "R510") (pin "1") (pinfunction "1_1") (pintype "passive"))
      (node (ref "R511") (pin "1") (pinfunction "1_1") (pintype "passive"))
    )
    (net (code "14") (name "MSP430_SCL") (class "Default")
      (node (ref "IC100") (pin "2") (pinfunction "SCL_2") (pintype "bidirectional"))
      (node (ref "IC400") (pin "A1") (pinfunction "SCL_A1") (pintype "input"))
      (node (ref "IC500") (pin "17") (pinfunction "P1.7/UCB0SOMI/UCB0SCL/TA1.0_17") (pintype "bidirectional"))
      (node (ref "IC600") (pin "1") (pinfunction "SCL_1") (pintype "bidirectional"))
      (node (ref "LINK") (pin "5") (pinfunction "5_5") (pintype "passive"))
    )
    (net (code "15") (name "MSP430_SDA") (class "Default")
      (node (ref "IC100") (pin "4") (pinfunction "SDA_4") (pintype "bidirectional"))
      (node (ref "IC400") (pin "A2") (pinfunction "SDA_A2") (pintype "bidirectional"))
      (node (ref "IC500") (pin "16") (pinfunction "P1.6/UCB0SIMO/UCB0SDA/TA0.0_16") (pintype "bidirectional"))
      (node (ref "IC600") (pin "6") (pinfunction "SDA_6") (pintype "bidirectional"))
      (node (ref "LINK") (pin "4") (pinfunction "4_4") (pintype "passive"))
    )
    (net (code "16") (name "MSP430_TEST") (class "Default")
      (node (ref "IC500") (pin "11") (pinfunction "TEST/SBWTCK_11") (pintype "bidirectional"))
      (node (ref "PROG") (pin "2") (pinfunction "2_2") (pintype "passive"))
    )
    (net (code "17") (name "MSP430_VCORE") (class "Default")
      (node (ref "C510") (pin "1") (pinfunction "1_1") (pintype "passive"))
      (node (ref "IC500") (pin "18") (pinfunction "VCORE_18") (pintype "power_in"))
    )
    (net (code "18") (name "Net-(C350-Pad2)") (class "Default")
      (node (ref "C350") (pin "2") (pinfunction "2_2") (pintype "passive"))
      (node (ref "C351") (pin "2") (pinfunction "2_2") (pintype "passive"))
      (node (ref "L350") (pin "2") (pinfunction "2_2") (pintype "passive"))
    )
    (net (code "19") (name "Net-(F300-UNBAL)") (class "Default")
      (node (ref "F300") (pin "1") (pinfunction "UNBAL_1") (pintype "passive"))
      (node (ref "L350") (pin "1") (pinfunction "1_1") (pintype "passive"))
    )
    (net (code "20") (name "Net-(IC200-LBOOST)") (class "Default")
      (node (ref "IC200") (pin "20") (pinfunction "LBOOST_20") (pintype "input"))
      (node (ref "L200") (pin "2") (pinfunction "2_2") (pintype "passive"))
    )
    (net (code "21") (name "Net-(IC200-LBUCK)") (class "Default")
      (node (ref "IC200") (pin "16") (pinfunction "LBUCK_16") (pintype "passive"))
      (node (ref "L210") (pin "1") (pinfunction "1_1") (pintype "passive"))
    )
    (net (code "22") (name "Net-(IC200-OK_HYST)") (class "Default")
      (node (ref "IC200") (pin "10") (pinfunction "OK_HYST_10") (pintype "input"))
      (node (ref "R220") (pin "1") (pinfunction "1_1") (pintype "passive"))
      (node (ref "R221") (pin "2") (pinfunction "2_2") (pintype "passive"))
    )
    (net (code "23") (name "Net-(IC200-OK_PROG)") (class "Default")
      (node (ref "IC200") (pin "11") (pinfunction "OK_PROG_11") (pintype "input"))
      (node (ref "R221") (pin "1") (pinfunction "1_1") (pintype "passive"))
      (node (ref "R222") (pin "2") (pinfunction "2_2") (pintype "passive"))
    )
    (net (code "24") (name "Net-(IC200-VBAT)") (class "Default")
      (node (ref "BAT") (pin "1") (pinfunction "1_1") (pintype "passive"))
      (node (ref "IC200") (pin "18") (pinfunction "VBAT_18") (pintype "bidirectional"))
    )
    (net (code "25") (name "Net-(IC200-VBAT_OV)") (class "Default")
      (node (ref "IC200") (pin "7") (pinfunction "VBAT_OV_7") (pintype "input"))
      (node (ref "R210") (pin "2") (pinfunction "2_2") (pintype "passive"))
      (node (ref "R211") (pin "2") (pinfunction "2_2") (pintype "passive"))
    )
    (net (code "26") (name "Net-(IC200-VOUT)") (class "Default")
      (node (ref "!PROG") (pin "2") (pinfunction "2_2") (pintype "passive"))
      (node (ref "C210") (pin "1") (pinfunction "1_1") (pintype "passive"))
      (node (ref "IC200") (pin "14") (pinfunction "VOUT_14") (pintype "power_in"))
      (node (ref "L210") (pin "2") (pinfunction "2_2") (pintype "passive"))
    )
    (net (code "27") (name "Net-(IC200-VOUT_EN)") (class "Default")
      (node (ref "IC200") (pin "6") (pinfunction "VOUT_EN_6") (pintype "input"))
      (node (ref "R200") (pin "2") (pinfunction "2_2") (pintype "passive"))
      (node (ref "R201") (pin "1") (pinfunction "1_1") (pintype "passive"))
    )
    (net (code "28") (name "Net-(IC200-VOUT_SET)") (class "Default")
      (node (ref "IC200") (pin "12") (pinfunction "VOUT_SET_12") (pintype "input"))
      (node (ref "R230") (pin "1") (pinfunction "1_1") (pintype "passive"))
      (node (ref "R231") (pin "2") (pinfunction "2_2") (pintype "passive"))
    )
    (net (code "29") (name "Net-(IC200-VRDIV)") (class "Default")
      (node (ref "IC200") (pin "8") (pinfunction "VRDIV_8") (pintype "output"))
      (node (ref "R210") (pin "1") (pinfunction "1_1") (pintype "passive"))
      (node (ref "R220") (pin "2") (pinfunction "2_2") (pintype "passive"))
      (node (ref "R230") (pin "2") (pinfunction "2_2") (pintype "passive"))
    )
    (net (code "30") (name "Net-(IC200-VREF_SAMP)") (class "Default")
      (node (ref "C200") (pin "1") (pinfunction "1_1") (pintype "passive"))
      (node (ref "IC200") (pin "4") (pinfunction "VREF_SAMP_4") (pintype "input"))
    )
    (net (code "31") (name "Net-(IC300-DCOUPL)") (class "Default")
      (node (ref "C310") (pin "1") (pinfunction "1_1") (pintype "passive"))
      (node (ref "IC300") (pin "5") (pinfunction "DCOUPL_5") (pintype "passive"))
    )
    (net (code "32") (name "Net-(IC300-RBIAS)") (class "Default")
      (node (ref "IC300") (pin "17") (pinfunction "RBIAS_17") (pintype "passive"))
      (node (ref "R300") (pin "2") (pinfunction "2_2") (pintype "passive"))
    )
    (net (code "33") (name "Net-(IC300-RF_N)") (class "Default")
      (node (ref "F300") (pin "3") (pinfunction "BAL_3") (pintype "passive"))
      (node (ref "IC300") (pin "13") (pinfunction "RF_N_13") (pintype "passive"))
    )
    (net (code "34") (name "Net-(IC300-RF_P)") (class "Default")
      (node (ref "F300") (pin "4") (pinfunction "BAL_4") (pintype "passive"))
      (node (ref "IC300") (pin "12") (pinfunction "RF_P_12") (pintype "passive"))
    )
    (net (code "35") (name "Net-(IC300-XOSC_Q1)") (class "Default")
      (node (ref "C320") (pin "1") (pinfunction "1_1") (pintype "passive"))
      (node (ref "IC300") (pin "8") (pinfunction "XOSC_Q1_8") (pintype "passive"))
      (node (ref "X320") (pin "3") (pinfunction "2_3") (pintype "passive"))
    )
    (net (code "36") (name "Net-(IC300-XOSC_Q2)") (class "Default")
      (node (ref "C321") (pin "1") (pinfunction "1_1") (pintype "passive"))
      (node (ref "IC300") (pin "10") (pinfunction "XOSC_Q2_10") (pintype "passive"))
      (node (ref "X320") (pin "1") (pinfunction "1_1") (pintype "passive"))
    )
    (net (code "37") (name "Net-(IC700-DELAY_M_DRV)") (class "Default")
      (node (ref "IC700") (pin "3") (pinfunction "DELAY_M_DRV_3") (pintype "input"))
      (node (ref "R700") (pin "1") (pinfunction "1_1") (pintype "passive"))
      (node (ref "S1") (pin "1") (pinfunction "1.1_1") (pintype "passive"))
      (node (ref "S1") (pin "2") (pinfunction "1.2_2") (pintype "passive"))
    )
    (net (code "38") (name "Net-(IC700-EN_ONE_SHOT)") (class "Default")
      (node (ref "IC700") (pin "6") (pinfunction "EN_ONE_SHOT_6") (pintype "output"))
      (node (ref "R710") (pin "1") (pinfunction "1_1") (pintype "passive"))
      (node (ref "R711") (pin "2") (pinfunction "2_2") (pintype "passive"))
    )
    (net (code "39") (name "Net-(U$1-P$1)") (class "Default")
      (node (ref "C351") (pin "1") (pinfunction "1_1") (pintype "passive"))
      (node (ref "C352") (pin "1") (pinfunction "1_1") (pintype "passive"))
      (node (ref "U$1") (pin "1") (pinfunction "P$1_1") (pintype "bidirectional"))
    )
    (net (code "40") (name "SOLAR_P") (class "Default")
      (node (ref "C201") (pin "1") (pinfunction "1_1") (pintype "passive"))
      (node (ref "IC200") (pin "2") (pinfunction "VIN_DC_2") (pintype "power_in"))
      (node (ref "L200") (pin "1") (pinfunction "1_1") (pintype "passive"))
      (node (ref "LINK") (pin "1") (pinfunction "1_1") (pintype "passive"))
    )
    (net (code "41") (name "TPL5111_DONE") (class "Default")
      (node (ref "IC500") (pin "22") (pinfunction "PJ.5/XOUT_22") (pintype "bidirectional"))
      (node (ref "IC700") (pin "4") (pinfunction "DONE_4") (pintype "input"))
    )
    (net (code "42") (name "TPL5111_DRV") (class "Default")
      (node (ref "IC700") (pin "5") (pinfunction "DRV_5") (pintype "output"))
      (node (ref "R201") (pin "2") (pinfunction "2_2") (pintype "passive"))
      (node (ref "R510") (pin "2") (pinfunction "2_2") (pintype "passive"))
    )
    (net (code "43") (name "VCC") (class "Default")
      (node (ref "!PROG") (pin "1") (pinfunction "1_1") (pintype "passive"))
      (node (ref "C100") (pin "1") (pinfunction "1_1") (pintype "passive"))
      (node (ref "C101") (pin "1") (pinfunction "1_1") (pintype "passive"))
      (node (ref "C300") (pin "1") (pinfunction "1_1") (pintype "passive"))
      (node (ref "C301") (pin "1") (pinfunction "1_1") (pintype "passive"))
      (node (ref "C302") (pin "1") (pinfunction "1_1") (pintype "passive"))
      (node (ref "C400") (pin "1") (pinfunction "1_1") (pintype "passive"))
      (node (ref "C500") (pin "1") (pinfunction "1_1") (pintype "passive"))
      (node (ref "C501") (pin "1") (pinfunction "1_1") (pintype "passive"))
      (node (ref "C600") (pin "1") (pinfunction "1_1") (pintype "passive"))
      (node (ref "IC100") (pin "1") (pinfunction "VDD_IO_1") (pintype "power_in"))
      (node (ref "IC100") (pin "10") (pinfunction "VDD_10") (pintype "power_in"))
      (node (ref "IC100") (pin "6") (pinfunction "CS_6") (pintype "bidirectional"))
      (node (ref "IC300") (pin "11") (pinfunction "AVDD_3_11") (pintype "power_in"))
      (node (ref "IC300") (pin "14") (pinfunction "AVDD_4_14") (pintype "power_in"))
      (node (ref "IC300") (pin "15") (pinfunction "AVDD_15") (pintype "power_in"))
      (node (ref "IC300") (pin "18") (pinfunction "DGUARD_18") (pintype "passive"))
      (node (ref "IC300") (pin "4") (pinfunction "DVDD_4") (pintype "power_in"))
      (node (ref "IC300") (pin "9") (pinfunction "AVDD_2_9") (pintype "power_in"))
      (node (ref "IC400") (pin "B1") (pinfunction "VDD_B1") (pintype "power_in"))
      (node (ref "IC500") (pin "20") (pinfunction "DVCC_20") (pintype "power_in"))
      (node (ref "IC500") (pin "24") (pinfunction "AVCC_24") (pintype "power_in"))
      (node (ref "IC600") (pin "5") (pinfunction "V+_5") (pintype "power_in"))
      (node (ref "LINK") (pin "3") (pinfunction "3_3") (pintype "passive"))
      (node (ref "PROG") (pin "1") (pinfunction "1_1") (pintype "passive"))
      (node (ref "R500") (pin "2") (pinfunction "2_2") (pintype "passive"))
    )
    (net (code "44") (name "unconnected-(ADRESS-Pad3)") (class "Default")
      (node (ref "ADRESS") (pin "3") (pinfunction "3_3") (pintype "passive"))
    )
    (net (code "45") (name "unconnected-(IC400-DNC-PadC2)") (class "Default")
      (node (ref "IC400") (pin "C2") (pinfunction "DNC_C2") (pintype "passive"))
    )
    (net (code "46") (name "~{CC110L_CS}") (class "Default")
      (node (ref "IC300") (pin "7") (pinfunction "CSN_7") (pintype "passive"))
      (node (ref "IC500") (pin "7") (pinfunction "PJ.0/TDO/TB0OUTH/SMCLK/CD6_7") (pintype "bidirectional"))
    )
    (net (code "47") (name "~{HDC1000_INT}") (class "Default")
      (node (ref "IC400") (pin "D2") (pinfunction "DRDY_N_D2") (pintype "input"))
      (node (ref "IC500") (pin "3") (pinfunction "P1.2/TA1.1/TA0CLK/CDOUT/A2*/CD2_3") (pintype "bidirectional"))
    )
    (net (code "48") (name "~{LINK_INT}") (class "Default")
      (node (ref "IC500") (pin "5") (pinfunction "P1.4/TB0.1/UCA0STE/A4*/CD4_5") (pintype "bidirectional"))
      (node (ref "LINK") (pin "6") (pinfunction "6_6") (pintype "passive"))
    )
    (net (code "49") (name "~{MSP430_RST}") (class "Default")
      (node (ref "IC500") (pin "12") (pinfunction "*RST/NMI/SBWTDIO_12") (pintype "bidirectional"))
      (node (ref "PROG") (pin "3") (pinfunction "3_3") (pintype "passive"))
      (node (ref "R500") (pin "1") (pinfunction "1_1") (pintype "passive"))
    )
    (net (code "50") (name "~{TMP102_ALERT}") (class "Default")
      (node (ref "IC500") (pin "1") (pinfunction "P1.0/TA0.1/DMAE0/RTCCLK/A0*/CD0/VEREF-*_1") (pintype "bidirectional"))
      (node (ref "IC600") (pin "3") (pinfunction "ALERT_3") (pintype "output"))
    )
  )
)
